# 3V-16V_-5V_Regulator.net
KiCad netlist of a schematic drawn in Altium Designer
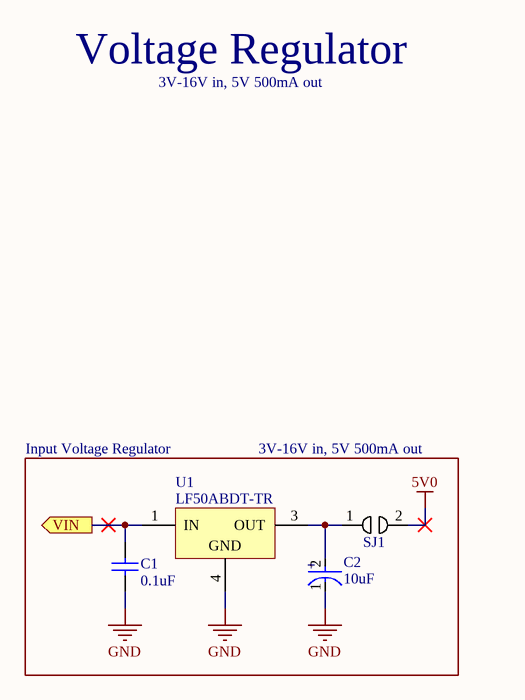
[diagram p0: (3V-16V)-5V Regulator.SchDoc]

(export (version "E")
  (design (tool "Eeschema 10.0.6"))
  (components
    (comp (ref "C1")
      (value "0.1uF")
      (footprint "CAPC2013X95X45ML10T25")
      (description "Chip Capacitor, 0.1 uF, +/- 10%, 50 V, 0805 (2012 Metric), RoHS, Tape and Reel")
      (fields
        (field (name "MANUFACTURER") "Samsung Electro-Mechanics")
        (field (name "MANUFACTURER PART NUMBER") "CL21B104KBCNNNC")
      )
      (libsource (lib "Altium Content Vault") (part "CAP-NP-2"))
    )
    (comp (ref "C2")
      (value "10uF")
      (footprint "FP-T491C-MFG")
      (description "CAP TANT 10UF 10% 25V 2312")
      (fields (field (name "TOLERANCE") "10%") (field (name "MANUFACTURER PART NUMBER") "T491C106K025AT"))
      (libsource (lib "Altium Content Vault") (part "203bc49f2ac43e59fd269a8c329ed05"))
    )
    (comp (ref "SJ1")
      (value "Jumper")
      (footprint "35MIL CIRCULAR")
      (description "Solder Jumper to connect or disconnect a trace.")
      (libsource (lib "Solder Jumpers") (part "Jumper"))
    )
    (comp (ref "U1")
      (value "LF50ABDT-TR")
      (footprint "TO-252_M")
      (description "500mA, Very Low Drop (0.45V) Voltage Regulator, 5V, 3-Pin DPAK, Tape and Reel")
      (fields (field (name "MANUFACTURER") "STMicroelectronics"))
      (libsource (lib "Altium Content Vault") (part "PM-REG-L4940-SOT3"))
    )
  )
  (nets
    (net (code "1") (name "/VIN") (class "Default")
      (node (ref "C1") (pin "1") (pinfunction "1_1") (pintype "passive"))
      (node (ref "U1") (pin "1") (pinfunction "IN_1") (pintype "power_in"))
    )
    (net (code "2") (name "5V0") (class "Default") (node (ref "SJ1") (pin "2") (pintype "passive")))
    (net (code "3") (name "GND") (class "Default")
      (node (ref "C1") (pin "2") (pinfunction "2_2") (pintype "passive"))
      (node (ref "C2") (pin "1") (pinfunction "C_1") (pintype "passive"))
      (node (ref "U1") (pin "4") (pinfunction "GND_4") (pintype "power_in"))
    )
    (net (code "4") (name "Net-(C2-A)") (class "Default")
      (node (ref "C2") (pin "2") (pinfunction "A_2") (pintype "passive"))
      (node (ref "SJ1") (pin "1") (pintype "passive"))
      (node (ref "U1") (pin "3") (pinfunction "OUT_3") (pintype "power_in"))
    )
  )
)
